# button_pad_6x10_v19.net
KiCad netlist of a schematic drawn in EAGLE
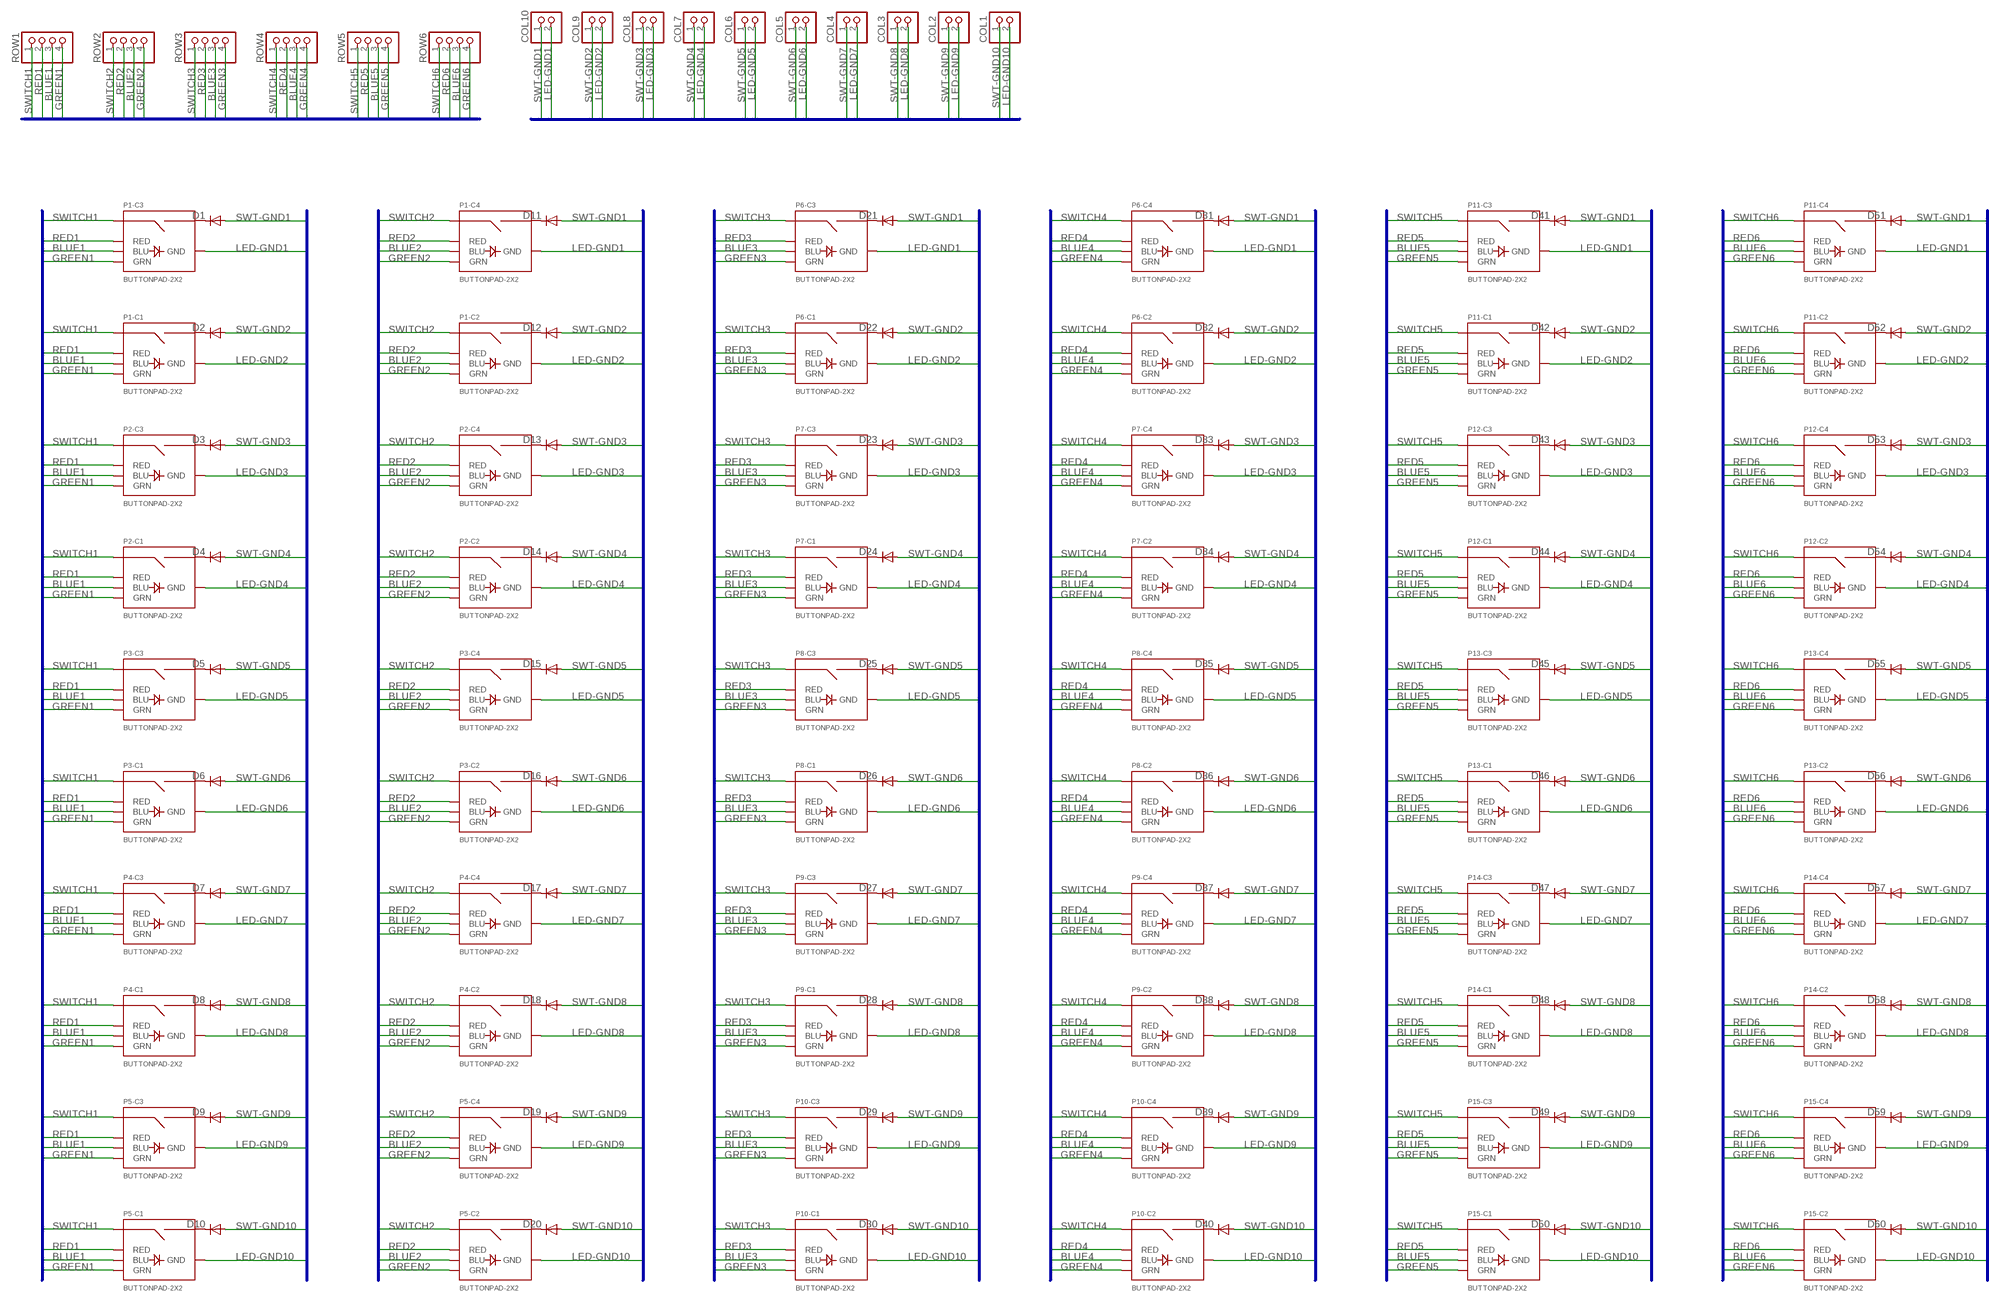
[diagram p0: schematic, sheet 1]

(export (version "E")
  (design (tool "Eeschema 10.0.6"))
  (components
    (comp (ref "COL1")
      (value "PINHD-1X2")
      (footprint "eagle-import:1X02")
      (libsource (lib "eagle-import") (part "PINHD-1X2"))
    )
    (comp (ref "COL2")
      (value "PINHD-1X2")
      (footprint "eagle-import:1X02")
      (libsource (lib "eagle-import") (part "PINHD-1X2"))
    )
    (comp (ref "COL3")
      (value "PINHD-1X2")
      (footprint "eagle-import:1X02")
      (libsource (lib "eagle-import") (part "PINHD-1X2"))
    )
    (comp (ref "COL4")
      (value "PINHD-1X2")
      (footprint "eagle-import:1X02")
      (libsource (lib "eagle-import") (part "PINHD-1X2"))
    )
    (comp (ref "COL5")
      (value "PINHD-1X2")
      (footprint "eagle-import:1X02")
      (libsource (lib "eagle-import") (part "PINHD-1X2"))
    )
    (comp (ref "COL6")
      (value "PINHD-1X2")
      (footprint "eagle-import:1X02")
      (libsource (lib "eagle-import") (part "PINHD-1X2"))
    )
    (comp (ref "COL7")
      (value "PINHD-1X2")
      (footprint "eagle-import:1X02")
      (libsource (lib "eagle-import") (part "PINHD-1X2"))
    )
    (comp (ref "COL8")
      (value "PINHD-1X2")
      (footprint "eagle-import:1X02")
      (libsource (lib "eagle-import") (part "PINHD-1X2"))
    )
    (comp (ref "COL9")
      (value "PINHD-1X2")
      (footprint "eagle-import:1X02")
      (libsource (lib "eagle-import") (part "PINHD-1X2"))
    )
    (comp (ref "COL10")
      (value "PINHD-1X2")
      (footprint "eagle-import:1X02")
      (libsource (lib "eagle-import") (part "PINHD-1X2"))
    )
    (comp (ref "D1")
      (value "DIODE-1N4148")
      (footprint "eagle-import:DOIDE-1N4148")
      (libsource (lib "eagle-import") (part "DIODE-1N4148"))
    )
    (comp (ref "D2")
      (value "DIODE-1N4148")
      (footprint "eagle-import:DOIDE-1N4148")
      (libsource (lib "eagle-import") (part "DIODE-1N4148"))
    )
    (comp (ref "D3")
      (value "DIODE-1N4148")
      (footprint "eagle-import:DOIDE-1N4148")
      (libsource (lib "eagle-import") (part "DIODE-1N4148"))
    )
    (comp (ref "D4")
      (value "DIODE-1N4148")
      (footprint "eagle-import:DOIDE-1N4148")
      (libsource (lib "eagle-import") (part "DIODE-1N4148"))
    )
    (comp (ref "D5")
      (value "DIODE-1N4148")
      (footprint "eagle-import:DOIDE-1N4148")
      (libsource (lib "eagle-import") (part "DIODE-1N4148"))
    )
    (comp (ref "D6")
      (value "DIODE-1N4148")
      (footprint "eagle-import:DOIDE-1N4148")
      (libsource (lib "eagle-import") (part "DIODE-1N4148"))
    )
    (comp (ref "D7")
      (value "DIODE-1N4148")
      (footprint "eagle-import:DOIDE-1N4148")
      (libsource (lib "eagle-import") (part "DIODE-1N4148"))
    )
    (comp (ref "D8")
      (value "DIODE-1N4148")
      (footprint "eagle-import:DOIDE-1N4148")
      (libsource (lib "eagle-import") (part "DIODE-1N4148"))
    )
    (comp (ref "D9")
      (value "DIODE-1N4148")
      (footprint "eagle-import:DOIDE-1N4148")
      (libsource (lib "eagle-import") (part "DIODE-1N4148"))
    )
    (comp (ref "D10")
      (value "DIODE-1N4148")
      (footprint "eagle-import:DOIDE-1N4148")
      (libsource (lib "eagle-import") (part "DIODE-1N4148"))
    )
    (comp (ref "D11")
      (value "DIODE-1N4148")
      (footprint "eagle-import:DOIDE-1N4148")
      (libsource (lib "eagle-import") (part "DIODE-1N4148"))
    )
    (comp (ref "D12")
      (value "DIODE-1N4148")
      (footprint "eagle-import:DOIDE-1N4148")
      (libsource (lib "eagle-import") (part "DIODE-1N4148"))
    )
    (comp (ref "D13")
      (value "DIODE-1N4148")
      (footprint "eagle-import:DOIDE-1N4148")
      (libsource (lib "eagle-import") (part "DIODE-1N4148"))
    )
    (comp (ref "D14")
      (value "DIODE-1N4148")
      (footprint "eagle-import:DOIDE-1N4148")
      (libsource (lib "eagle-import") (part "DIODE-1N4148"))
    )
    (comp (ref "D15")
      (value "DIODE-1N4148")
      (footprint "eagle-import:DOIDE-1N4148")
      (libsource (lib "eagle-import") (part "DIODE-1N4148"))
    )
    (comp (ref "D16")
      (value "DIODE-1N4148")
      (footprint "eagle-import:DOIDE-1N4148")
      (libsource (lib "eagle-import") (part "DIODE-1N4148"))
    )
    (comp (ref "D17")
      (value "DIODE-1N4148")
      (footprint "eagle-import:DOIDE-1N4148")
      (libsource (lib "eagle-import") (part "DIODE-1N4148"))
    )
    (comp (ref "D18")
      (value "DIODE-1N4148")
      (footprint "eagle-import:DOIDE-1N4148")
      (libsource (lib "eagle-import") (part "DIODE-1N4148"))
    )
    (comp (ref "D19")
      (value "DIODE-1N4148")
      (footprint "eagle-import:DOIDE-1N4148")
      (libsource (lib "eagle-import") (part "DIODE-1N4148"))
    )
    (comp (ref "D20")
      (value "DIODE-1N4148")
      (footprint "eagle-import:DOIDE-1N4148")
      (libsource (lib "eagle-import") (part "DIODE-1N4148"))
    )
    (comp (ref "D21")
      (value "DIODE-1N4148")
      (footprint "eagle-import:DOIDE-1N4148")
      (libsource (lib "eagle-import") (part "DIODE-1N4148"))
    )
    (comp (ref "D22")
      (value "DIODE-1N4148")
      (footprint "eagle-import:DOIDE-1N4148")
      (libsource (lib "eagle-import") (part "DIODE-1N4148"))
    )
    (comp (ref "D23")
      (value "DIODE-1N4148")
      (footprint "eagle-import:DOIDE-1N4148")
      (libsource (lib "eagle-import") (part "DIODE-1N4148"))
    )
    (comp (ref "D24")
      (value "DIODE-1N4148")
      (footprint "eagle-import:DOIDE-1N4148")
      (libsource (lib "eagle-import") (part "DIODE-1N4148"))
    )
    (comp (ref "D25")
      (value "DIODE-1N4148")
      (footprint "eagle-import:DOIDE-1N4148")
      (libsource (lib "eagle-import") (part "DIODE-1N4148"))
    )
    (comp (ref "D26")
      (value "DIODE-1N4148")
      (footprint "eagle-import:DOIDE-1N4148")
      (libsource (lib "eagle-import") (part "DIODE-1N4148"))
    )
    (comp (ref "D27")
      (value "DIODE-1N4148")
      (footprint "eagle-import:DOIDE-1N4148")
      (libsource (lib "eagle-import") (part "DIODE-1N4148"))
    )
    (comp (ref "D28")
      (value "DIODE-1N4148")
      (footprint "eagle-import:DOIDE-1N4148")
      (libsource (lib "eagle-import") (part "DIODE-1N4148"))
    )
    (comp (ref "D29")
      (value "DIODE-1N4148")
      (footprint "eagle-import:DOIDE-1N4148")
      (libsource (lib "eagle-import") (part "DIODE-1N4148"))
    )
    (comp (ref "D30")
      (value "DIODE-1N4148")
      (footprint "eagle-import:DOIDE-1N4148")
      (libsource (lib "eagle-import") (part "DIODE-1N4148"))
    )
    (comp (ref "D31")
      (value "DIODE-1N4148")
      (footprint "eagle-import:DOIDE-1N4148")
      (libsource (lib "eagle-import") (part "DIODE-1N4148"))
    )
    (comp (ref "D32")
      (value "DIODE-1N4148")
      (footprint "eagle-import:DOIDE-1N4148")
      (libsource (lib "eagle-import") (part "DIODE-1N4148"))
    )
    (comp (ref "D33")
      (value "DIODE-1N4148")
      (footprint "eagle-import:DOIDE-1N4148")
      (libsource (lib "eagle-import") (part "DIODE-1N4148"))
    )
    (comp (ref "D34")
      (value "DIODE-1N4148")
      (footprint "eagle-import:DOIDE-1N4148")
      (libsource (lib "eagle-import") (part "DIODE-1N4148"))
    )
    (comp (ref "D35")
      (value "DIODE-1N4148")
      (footprint "eagle-import:DOIDE-1N4148")
      (libsource (lib "eagle-import") (part "DIODE-1N4148"))
    )
    (comp (ref "D36")
      (value "DIODE-1N4148")
      (footprint "eagle-import:DOIDE-1N4148")
      (libsource (lib "eagle-import") (part "DIODE-1N4148"))
    )
    (comp (ref "D37")
      (value "DIODE-1N4148")
      (footprint "eagle-import:DOIDE-1N4148")
      (libsource (lib "eagle-import") (part "DIODE-1N4148"))
    )
    (comp (ref "D38")
      (value "DIODE-1N4148")
      (footprint "eagle-import:DOIDE-1N4148")
      (libsource (lib "eagle-import") (part "DIODE-1N4148"))
    )
    (comp (ref "D39")
      (value "DIODE-1N4148")
      (footprint "eagle-import:DOIDE-1N4148")
      (libsource (lib "eagle-import") (part "DIODE-1N4148"))
    )
    (comp (ref "D40")
      (value "DIODE-1N4148")
      (footprint "eagle-import:DOIDE-1N4148")
      (libsource (lib "eagle-import") (part "DIODE-1N4148"))
    )
    (comp (ref "D41")
      (value "DIODE-1N4148")
      (footprint "eagle-import:DOIDE-1N4148")
      (libsource (lib "eagle-import") (part "DIODE-1N4148"))
    )
    (comp (ref "D42")
      (value "DIODE-1N4148")
      (footprint "eagle-import:DOIDE-1N4148")
      (libsource (lib "eagle-import") (part "DIODE-1N4148"))
    )
    (comp (ref "D43")
      (value "DIODE-1N4148")
      (footprint "eagle-import:DOIDE-1N4148")
      (libsource (lib "eagle-import") (part "DIODE-1N4148"))
    )
    (comp (ref "D44")
      (value "DIODE-1N4148")
      (footprint "eagle-import:DOIDE-1N4148")
      (libsource (lib "eagle-import") (part "DIODE-1N4148"))
    )
    (comp (ref "D45")
      (value "DIODE-1N4148")
      (footprint "eagle-import:DOIDE-1N4148")
      (libsource (lib "eagle-import") (part "DIODE-1N4148"))
    )
    (comp (ref "D46")
      (value "DIODE-1N4148")
      (footprint "eagle-import:DOIDE-1N4148")
      (libsource (lib "eagle-import") (part "DIODE-1N4148"))
    )
    (comp (ref "D47")
      (value "DIODE-1N4148")
      (footprint "eagle-import:DOIDE-1N4148")
      (libsource (lib "eagle-import") (part "DIODE-1N4148"))
    )
    (comp (ref "D48")
      (value "DIODE-1N4148")
      (footprint "eagle-import:DOIDE-1N4148")
      (libsource (lib "eagle-import") (part "DIODE-1N4148"))
    )
    (comp (ref "D49")
      (value "DIODE-1N4148")
      (footprint "eagle-import:DOIDE-1N4148")
      (libsource (lib "eagle-import") (part "DIODE-1N4148"))
    )
    (comp (ref "D50")
      (value "DIODE-1N4148")
      (footprint "eagle-import:DOIDE-1N4148")
      (libsource (lib "eagle-import") (part "DIODE-1N4148"))
    )
    (comp (ref "D51")
      (value "DIODE-1N4148")
      (footprint "eagle-import:DOIDE-1N4148")
      (libsource (lib "eagle-import") (part "DIODE-1N4148"))
    )
    (comp (ref "D52")
      (value "DIODE-1N4148")
      (footprint "eagle-import:DOIDE-1N4148")
      (libsource (lib "eagle-import") (part "DIODE-1N4148"))
    )
    (comp (ref "D53")
      (value "DIODE-1N4148")
      (footprint "eagle-import:DOIDE-1N4148")
      (libsource (lib "eagle-import") (part "DIODE-1N4148"))
    )
    (comp (ref "D54")
      (value "DIODE-1N4148")
      (footprint "eagle-import:DOIDE-1N4148")
      (libsource (lib "eagle-import") (part "DIODE-1N4148"))
    )
    (comp (ref "D55")
      (value "DIODE-1N4148")
      (footprint "eagle-import:DOIDE-1N4148")
      (libsource (lib "eagle-import") (part "DIODE-1N4148"))
    )
    (comp (ref "D56")
      (value "DIODE-1N4148")
      (footprint "eagle-import:DOIDE-1N4148")
      (libsource (lib "eagle-import") (part "DIODE-1N4148"))
    )
    (comp (ref "D57")
      (value "DIODE-1N4148")
      (footprint "eagle-import:DOIDE-1N4148")
      (libsource (lib "eagle-import") (part "DIODE-1N4148"))
    )
    (comp (ref "D58")
      (value "DIODE-1N4148")
      (footprint "eagle-import:DOIDE-1N4148")
      (libsource (lib "eagle-import") (part "DIODE-1N4148"))
    )
    (comp (ref "D59")
      (value "DIODE-1N4148")
      (footprint "eagle-import:DOIDE-1N4148")
      (libsource (lib "eagle-import") (part "DIODE-1N4148"))
    )
    (comp (ref "D60")
      (value "DIODE-1N4148")
      (footprint "eagle-import:DOIDE-1N4148")
      (libsource (lib "eagle-import") (part "DIODE-1N4148"))
    )
    (comp (ref "P1")
      (value "BUTTONPAD-2X2")
      (footprint "eagle-import:BUTTONPAD-2X2")
      (libsource (lib "eagle-import") (part "BUTTONPAD-2X2"))
    )
    (comp (ref "P2")
      (value "BUTTONPAD-2X2")
      (footprint "eagle-import:BUTTONPAD-2X2")
      (libsource (lib "eagle-import") (part "BUTTONPAD-2X2"))
    )
    (comp (ref "P3")
      (value "BUTTONPAD-2X2")
      (footprint "eagle-import:BUTTONPAD-2X2")
      (libsource (lib "eagle-import") (part "BUTTONPAD-2X2"))
    )
    (comp (ref "P4")
      (value "BUTTONPAD-2X2")
      (footprint "eagle-import:BUTTONPAD-2X2")
      (libsource (lib "eagle-import") (part "BUTTONPAD-2X2"))
    )
    (comp (ref "P5")
      (value "BUTTONPAD-2X2")
      (footprint "eagle-import:BUTTONPAD-2X2")
      (libsource (lib "eagle-import") (part "BUTTONPAD-2X2"))
    )
    (comp (ref "P6")
      (value "BUTTONPAD-2X2")
      (footprint "eagle-import:BUTTONPAD-2X2")
      (libsource (lib "eagle-import") (part "BUTTONPAD-2X2"))
    )
    (comp (ref "P7")
      (value "BUTTONPAD-2X2")
      (footprint "eagle-import:BUTTONPAD-2X2")
      (libsource (lib "eagle-import") (part "BUTTONPAD-2X2"))
    )
    (comp (ref "P8")
      (value "BUTTONPAD-2X2")
      (footprint "eagle-import:BUTTONPAD-2X2")
      (libsource (lib "eagle-import") (part "BUTTONPAD-2X2"))
    )
    (comp (ref "P9")
      (value "BUTTONPAD-2X2")
      (footprint "eagle-import:BUTTONPAD-2X2")
      (libsource (lib "eagle-import") (part "BUTTONPAD-2X2"))
    )
    (comp (ref "P10")
      (value "BUTTONPAD-2X2")
      (footprint "eagle-import:BUTTONPAD-2X2")
      (libsource (lib "eagle-import") (part "BUTTONPAD-2X2"))
    )
    (comp (ref "P11")
      (value "BUTTONPAD-2X2")
      (footprint "eagle-import:BUTTONPAD-2X2")
      (libsource (lib "eagle-import") (part "BUTTONPAD-2X2"))
    )
    (comp (ref "P12")
      (value "BUTTONPAD-2X2")
      (footprint "eagle-import:BUTTONPAD-2X2")
      (libsource (lib "eagle-import") (part "BUTTONPAD-2X2"))
    )
    (comp (ref "P13")
      (value "BUTTONPAD-2X2")
      (footprint "eagle-import:BUTTONPAD-2X2")
      (libsource (lib "eagle-import") (part "BUTTONPAD-2X2"))
    )
    (comp (ref "P14")
      (value "BUTTONPAD-2X2")
      (footprint "eagle-import:BUTTONPAD-2X2")
      (libsource (lib "eagle-import") (part "BUTTONPAD-2X2"))
    )
    (comp (ref "P15")
      (value "BUTTONPAD-2X2")
      (footprint "eagle-import:BUTTONPAD-2X2")
      (libsource (lib "eagle-import") (part "BUTTONPAD-2X2"))
    )
    (comp (ref "ROW1")
      (value "PINHD-1X4")
      (footprint "eagle-import:1X04")
      (libsource (lib "eagle-import") (part "PINHD-1X4"))
    )
    (comp (ref "ROW2")
      (value "PINHD-1X4")
      (footprint "eagle-import:1X04")
      (libsource (lib "eagle-import") (part "PINHD-1X4"))
    )
    (comp (ref "ROW3")
      (value "PINHD-1X4")
      (footprint "eagle-import:1X04")
      (libsource (lib "eagle-import") (part "PINHD-1X4"))
    )
    (comp (ref "ROW4")
      (value "PINHD-1X4")
      (footprint "eagle-import:1X04")
      (libsource (lib "eagle-import") (part "PINHD-1X4"))
    )
    (comp (ref "ROW5")
      (value "PINHD-1X4")
      (footprint "eagle-import:1X04")
      (libsource (lib "eagle-import") (part "PINHD-1X4"))
    )
    (comp (ref "ROW6")
      (value "PINHD-1X4")
      (footprint "eagle-import:1X04")
      (libsource (lib "eagle-import") (part "PINHD-1X4"))
    )
  )
  (nets
    (net (code "1") (name "/BLUE1") (class "Default")
      (node (ref "P1") (pin "BLU1") (pinfunction "BLU_BLU1") (pintype "bidirectional"))
      (node (ref "P1") (pin "BLU3") (pinfunction "BLU_BLU3") (pintype "bidirectional"))
      (node (ref "P2") (pin "BLU1") (pinfunction "BLU_BLU1") (pintype "bidirectional"))
      (node (ref "P2") (pin "BLU3") (pinfunction "BLU_BLU3") (pintype "bidirectional"))
      (node (ref "P3") (pin "BLU1") (pinfunction "BLU_BLU1") (pintype "bidirectional"))
      (node (ref "P3") (pin "BLU3") (pinfunction "BLU_BLU3") (pintype "bidirectional"))
      (node (ref "P4") (pin "BLU1") (pinfunction "BLU_BLU1") (pintype "bidirectional"))
      (node (ref "P4") (pin "BLU3") (pinfunction "BLU_BLU3") (pintype "bidirectional"))
      (node (ref "P5") (pin "BLU1") (pinfunction "BLU_BLU1") (pintype "bidirectional"))
      (node (ref "P5") (pin "BLU3") (pinfunction "BLU_BLU3") (pintype "bidirectional"))
      (node (ref "ROW1") (pin "3") (pinfunction "3_3") (pintype "passive"))
    )
    (net (code "2") (name "/BLUE2") (class "Default")
      (node (ref "P1") (pin "BLU2") (pinfunction "BLU_BLU2") (pintype "bidirectional"))
      (node (ref "P1") (pin "BLU4") (pinfunction "BLU_BLU4") (pintype "bidirectional"))
      (node (ref "P2") (pin "BLU2") (pinfunction "BLU_BLU2") (pintype "bidirectional"))
      (node (ref "P2") (pin "BLU4") (pinfunction "BLU_BLU4") (pintype "bidirectional"))
      (node (ref "P3") (pin "BLU2") (pinfunction "BLU_BLU2") (pintype "bidirectional"))
      (node (ref "P3") (pin "BLU4") (pinfunction "BLU_BLU4") (pintype "bidirectional"))
      (node (ref "P4") (pin "BLU2") (pinfunction "BLU_BLU2") (pintype "bidirectional"))
      (node (ref "P4") (pin "BLU4") (pinfunction "BLU_BLU4") (pintype "bidirectional"))
      (node (ref "P5") (pin "BLU2") (pinfunction "BLU_BLU2") (pintype "bidirectional"))
      (node (ref "P5") (pin "BLU4") (pinfunction "BLU_BLU4") (pintype "bidirectional"))
      (node (ref "ROW2") (pin "3") (pinfunction "3_3") (pintype "passive"))
    )
    (net (code "3") (name "/BLUE3") (class "Default")
      (node (ref "P10") (pin "BLU1") (pinfunction "BLU_BLU1") (pintype "bidirectional"))
      (node (ref "P10") (pin "BLU3") (pinfunction "BLU_BLU3") (pintype "bidirectional"))
      (node (ref "P6") (pin "BLU1") (pinfunction "BLU_BLU1") (pintype "bidirectional"))
      (node (ref "P6") (pin "BLU3") (pinfunction "BLU_BLU3") (pintype "bidirectional"))
      (node (ref "P7") (pin "BLU1") (pinfunction "BLU_BLU1") (pintype "bidirectional"))
      (node (ref "P7") (pin "BLU3") (pinfunction "BLU_BLU3") (pintype "bidirectional"))
      (node (ref "P8") (pin "BLU1") (pinfunction "BLU_BLU1") (pintype "bidirectional"))
      (node (ref "P8") (pin "BLU3") (pinfunction "BLU_BLU3") (pintype "bidirectional"))
      (node (ref "P9") (pin "BLU1") (pinfunction "BLU_BLU1") (pintype "bidirectional"))
      (node (ref "P9") (pin "BLU3") (pinfunction "BLU_BLU3") (pintype "bidirectional"))
      (node (ref "ROW3") (pin "3") (pinfunction "3_3") (pintype "passive"))
    )
    (net (code "4") (name "/BLUE4") (class "Default")
      (node (ref "P10") (pin "BLU2") (pinfunction "BLU_BLU2") (pintype "bidirectional"))
      (node (ref "P10") (pin "BLU4") (pinfunction "BLU_BLU4") (pintype "bidirectional"))
      (node (ref "P6") (pin "BLU2") (pinfunction "BLU_BLU2") (pintype "bidirectional"))
      (node (ref "P6") (pin "BLU4") (pinfunction "BLU_BLU4") (pintype "bidirectional"))
      (node (ref "P7") (pin "BLU2") (pinfunction "BLU_BLU2") (pintype "bidirectional"))
      (node (ref "P7") (pin "BLU4") (pinfunction "BLU_BLU4") (pintype "bidirectional"))
      (node (ref "P8") (pin "BLU2") (pinfunction "BLU_BLU2") (pintype "bidirectional"))
      (node (ref "P8") (pin "BLU4") (pinfunction "BLU_BLU4") (pintype "bidirectional"))
      (node (ref "P9") (pin "BLU2") (pinfunction "BLU_BLU2") (pintype "bidirectional"))
      (node (ref "P9") (pin "BLU4") (pinfunction "BLU_BLU4") (pintype "bidirectional"))
      (node (ref "ROW4") (pin "3") (pinfunction "3_3") (pintype "passive"))
    )
    (net (code "5") (name "/BLUE5") (class "Default")
      (node (ref "P11") (pin "BLU1") (pinfunction "BLU_BLU1") (pintype "bidirectional"))
      (node (ref "P11") (pin "BLU3") (pinfunction "BLU_BLU3") (pintype "bidirectional"))
      (node (ref "P12") (pin "BLU1") (pinfunction "BLU_BLU1") (pintype "bidirectional"))
      (node (ref "P12") (pin "BLU3") (pinfunction "BLU_BLU3") (pintype "bidirectional"))
      (node (ref "P13") (pin "BLU1") (pinfunction "BLU_BLU1") (pintype "bidirectional"))
      (node (ref "P13") (pin "BLU3") (pinfunction "BLU_BLU3") (pintype "bidirectional"))
      (node (ref "P14") (pin "BLU1") (pinfunction "BLU_BLU1") (pintype "bidirectional"))
      (node (ref "P14") (pin "BLU3") (pinfunction "BLU_BLU3") (pintype "bidirectional"))
      (node (ref "P15") (pin "BLU1") (pinfunction "BLU_BLU1") (pintype "bidirectional"))
      (node (ref "P15") (pin "BLU3") (pinfunction "BLU_BLU3") (pintype "bidirectional"))
      (node (ref "ROW5") (pin "3") (pinfunction "3_3") (pintype "passive"))
    )
    (net (code "6") (name "/BLUE6") (class "Default")
      (node (ref "P11") (pin "BLU2") (pinfunction "BLU_BLU2") (pintype "bidirectional"))
      (node (ref "P11") (pin "BLU4") (pinfunction "BLU_BLU4") (pintype "bidirectional"))
      (node (ref "P12") (pin "BLU2") (pinfunction "BLU_BLU2") (pintype "bidirectional"))
      (node (ref "P12") (pin "BLU4") (pinfunction "BLU_BLU4") (pintype "bidirectional"))
      (node (ref "P13") (pin "BLU2") (pinfunction "BLU_BLU2") (pintype "bidirectional"))
      (node (ref "P13") (pin "BLU4") (pinfunction "BLU_BLU4") (pintype "bidirectional"))
      (node (ref "P14") (pin "BLU2") (pinfunction "BLU_BLU2") (pintype "bidirectional"))
      (node (ref "P14") (pin "BLU4") (pinfunction "BLU_BLU4") (pintype "bidirectional"))
      (node (ref "P15") (pin "BLU2") (pinfunction "BLU_BLU2") (pintype "bidirectional"))
      (node (ref "P15") (pin "BLU4") (pinfunction "BLU_BLU4") (pintype "bidirectional"))
      (node (ref "ROW6") (pin "3") (pinfunction "3_3") (pintype "passive"))
    )
    (net (code "7") (name "/GREEN1") (class "Default")
      (node (ref "P1") (pin "GRN1") (pinfunction "GRN_GRN1") (pintype "bidirectional"))
      (node (ref "P1") (pin "GRN3") (pinfunction "GRN_GRN3") (pintype "bidirectional"))
      (node (ref "P2") (pin "GRN1") (pinfunction "GRN_GRN1") (pintype "bidirectional"))
      (node (ref "P2") (pin "GRN3") (pinfunction "GRN_GRN3") (pintype "bidirectional"))
      (node (ref "P3") (pin "GRN1") (pinfunction "GRN_GRN1") (pintype "bidirectional"))
      (node (ref "P3") (pin "GRN3") (pinfunction "GRN_GRN3") (pintype "bidirectional"))
      (node (ref "P4") (pin "GRN1") (pinfunction "GRN_GRN1") (pintype "bidirectional"))
      (node (ref "P4") (pin "GRN3") (pinfunction "GRN_GRN3") (pintype "bidirectional"))
      (node (ref "P5") (pin "GRN1") (pinfunction "GRN_GRN1") (pintype "bidirectional"))
      (node (ref "P5") (pin "GRN3") (pinfunction "GRN_GRN3") (pintype "bidirectional"))
      (node (ref "ROW1") (pin "4") (pinfunction "4_4") (pintype "passive"))
    )
    (net (code "8") (name "/GREEN2") (class "Default")
      (node (ref "P1") (pin "GRN2") (pinfunction "GRN_GRN2") (pintype "bidirectional"))
      (node (ref "P1") (pin "GRN4") (pinfunction "GRN_GRN4") (pintype "bidirectional"))
      (node (ref "P2") (pin "GRN2") (pinfunction "GRN_GRN2") (pintype "bidirectional"))
      (node (ref "P2") (pin "GRN4") (pinfunction "GRN_GRN4") (pintype "bidirectional"))
      (node (ref "P3") (pin "GRN2") (pinfunction "GRN_GRN2") (pintype "bidirectional"))
      (node (ref "P3") (pin "GRN4") (pinfunction "GRN_GRN4") (pintype "bidirectional"))
      (node (ref "P4") (pin "GRN2") (pinfunction "GRN_GRN2") (pintype "bidirectional"))
      (node (ref "P4") (pin "GRN4") (pinfunction "GRN_GRN4") (pintype "bidirectional"))
      (node (ref "P5") (pin "GRN2") (pinfunction "GRN_GRN2") (pintype "bidirectional"))
      (node (ref "P5") (pin "GRN4") (pinfunction "GRN_GRN4") (pintype "bidirectional"))
      (node (ref "ROW2") (pin "4") (pinfunction "4_4") (pintype "passive"))
    )
    (net (code "9") (name "/GREEN3") (class "Default")
      (node (ref "P10") (pin "GRN1") (pinfunction "GRN_GRN1") (pintype "bidirectional"))
      (node (ref "P10") (pin "GRN3") (pinfunction "GRN_GRN3") (pintype "bidirectional"))
      (node (ref "P6") (pin "GRN1") (pinfunction "GRN_GRN1") (pintype "bidirectional"))
      (node (ref "P6") (pin "GRN3") (pinfunction "GRN_GRN3") (pintype "bidirectional"))
      (node (ref "P7") (pin "GRN1") (pinfunction "GRN_GRN1") (pintype "bidirectional"))
      (node (ref "P7") (pin "GRN3") (pinfunction "GRN_GRN3") (pintype "bidirectional"))
      (node (ref "P8") (pin "GRN1") (pinfunction "GRN_GRN1") (pintype "bidirectional"))
      (node (ref "P8") (pin "GRN3") (pinfunction "GRN_GRN3") (pintype "bidirectional"))
      (node (ref "P9") (pin "GRN1") (pinfunction "GRN_GRN1") (pintype "bidirectional"))
      (node (ref "P9") (pin "GRN3") (pinfunction "GRN_GRN3") (pintype "bidirectional"))
      (node (ref "ROW3") (pin "4") (pinfunction "4_4") (pintype "passive"))
    )
    (net (code "10") (name "/GREEN4") (class "Default")
      (node (ref "P10") (pin "GRN2") (pinfunction "GRN_GRN2") (pintype "bidirectional"))
      (node (ref "P10") (pin "GRN4") (pinfunction "GRN_GRN4") (pintype "bidirectional"))
      (node (ref "P6") (pin "GRN2") (pinfunction "GRN_GRN2") (pintype "bidirectional"))
      (node (ref "P6") (pin "GRN4") (pinfunction "GRN_GRN4") (pintype "bidirectional"))
      (node (ref "P7") (pin "GRN2") (pinfunction "GRN_GRN2") (pintype "bidirectional"))
      (node (ref "P7") (pin "GRN4") (pinfunction "GRN_GRN4") (pintype "bidirectional"))
      (node (ref "P8") (pin "GRN2") (pinfunction "GRN_GRN2") (pintype "bidirectional"))
      (node (ref "P8") (pin "GRN4") (pinfunction "GRN_GRN4") (pintype "bidirectional"))
      (node (ref "P9") (pin "GRN2") (pinfunction "GRN_GRN2") (pintype "bidirectional"))
      (node (ref "P9") (pin "GRN4") (pinfunction "GRN_GRN4") (pintype "bidirectional"))
      (node (ref "ROW4") (pin "4") (pinfunction "4_4") (pintype "passive"))
    )
    (net (code "11") (name "/GREEN5") (class "Default")
      (node (ref "P11") (pin "GRN1") (pinfunction "GRN_GRN1") (pintype "bidirectional"))
      (node (ref "P11") (pin "GRN3") (pinfunction "GRN_GRN3") (pintype "bidirectional"))
      (node (ref "P12") (pin "GRN1") (pinfunction "GRN_GRN1") (pintype "bidirectional"))
      (node (ref "P12") (pin "GRN3") (pinfunction "GRN_GRN3") (pintype "bidirectional"))
      (node (ref "P13") (pin "GRN1") (pinfunction "GRN_GRN1") (pintype "bidirectional"))
      (node (ref "P13") (pin "GRN3") (pinfunction "GRN_GRN3") (pintype "bidirectional"))
      (node (ref "P14") (pin "GRN1") (pinfunction "GRN_GRN1") (pintype "bidirectional"))
      (node (ref "P14") (pin "GRN3") (pinfunction "GRN_GRN3") (pintype "bidirectional"))
      (node (ref "P15") (pin "GRN1") (pinfunction "GRN_GRN1") (pintype "bidirectional"))
      (node (ref "P15") (pin "GRN3") (pinfunction "GRN_GRN3") (pintype "bidirectional"))
      (node (ref "ROW5") (pin "4") (pinfunction "4_4") (pintype "passive"))
    )
    (net (code "12") (name "/GREEN6") (class "Default")
      (node (ref "P11") (pin "GRN2") (pinfunction "GRN_GRN2") (pintype "bidirectional"))
      (node (ref "P11") (pin "GRN4") (pinfunction "GRN_GRN4") (pintype "bidirectional"))
      (node (ref "P12") (pin "GRN2") (pinfunction "GRN_GRN2") (pintype "bidirectional"))
      (node (ref "P12") (pin "GRN4") (pinfunction "GRN_GRN4") (pintype "bidirectional"))
      (node (ref "P13") (pin "GRN2") (pinfunction "GRN_GRN2") (pintype "bidirectional"))
      (node (ref "P13") (pin "GRN4") (pinfunction "GRN_GRN4") (pintype "bidirectional"))
      (node (ref "P14") (pin "GRN2") (pinfunction "GRN_GRN2") (pintype "bidirectional"))
      (node (ref "P14") (pin "GRN4") (pinfunction "GRN_GRN4") (pintype "bidirectional"))
      (node (ref "P15") (pin "GRN2") (pinfunction "GRN_GRN2") (pintype "bidirectional"))
      (node (ref "P15") (pin "GRN4") (pinfunction "GRN_GRN4") (pintype "bidirectional"))
      (node (ref "ROW6") (pin "4") (pinfunction "4_4") (pintype "passive"))
    )
    (net (code "13") (name "/LED-GND1") (class "Default")
      (node (ref "COL10") (pin "2") (pinfunction "2_2") (pintype "passive"))
      (node (ref "P1") (pin "GND3") (pinfunction "GND_GND3") (pintype "bidirectional"))
      (node (ref "P1") (pin "GND4") (pinfunction "GND_GND4") (pintype "bidirectional"))
      (node (ref "P11") (pin "GND3") (pinfunction "GND_GND3") (pintype "bidirectional"))
      (node (ref "P11") (pin "GND4") (pinfunction "GND_GND4") (pintype "bidirectional"))
      (node (ref "P6") (pin "GND3") (pinfunction "GND_GND3") (pintype "bidirectional"))
      (node (ref "P6") (pin "GND4") (pinfunction "GND_GND4") (pintype "bidirectional"))
    )
    (net (code "14") (name "/LED-GND2") (class "Default")
      (node (ref "COL9") (pin "2") (pinfunction "2_2") (pintype "passive"))
      (node (ref "P1") (pin "GND1") (pinfunction "GND_GND1") (pintype "bidirectional"))
      (node (ref "P1") (pin "GND2") (pinfunction "GND_GND2") (pintype "bidirectional"))
      (node (ref "P11") (pin "GND1") (pinfunction "GND_GND1") (pintype "bidirectional"))
      (node (ref "P11") (pin "GND2") (pinfunction "GND_GND2") (pintype "bidirectional"))
      (node (ref "P6") (pin "GND1") (pinfunction "GND_GND1") (pintype "bidirectional"))
      (node (ref "P6") (pin "GND2") (pinfunction "GND_GND2") (pintype "bidirectional"))
    )
    (net (code "15") (name "/LED-GND3") (class "Default")
      (node (ref "COL8") (pin "2") (pinfunction "2_2") (pintype "passive"))
      (node (ref "P12") (pin "GND3") (pinfunction "GND_GND3") (pintype "bidirectional"))
      (node (ref "P12") (pin "GND4") (pinfunction "GND_GND4") (pintype "bidirectional"))
      (node (ref "P2") (pin "GND3") (pinfunction "GND_GND3") (pintype "bidirectional"))
      (node (ref "P2") (pin "GND4") (pinfunction "GND_GND4") (pintype "bidirectional"))
      (node (ref "P7") (pin "GND3") (pinfunction "GND_GND3") (pintype "bidirectional"))
      (node (ref "P7") (pin "GND4") (pinfunction "GND_GND4") (pintype "bidirectional"))
    )
    (net (code "16") (name "/LED-GND4") (class "Default")
      (node (ref "COL7") (pin "2") (pinfunction "2_2") (pintype "passive"))
      (node (ref "P12") (pin "GND1") (pinfunction "GND_GND1") (pintype "bidirectional"))
      (node (ref "P12") (pin "GND2") (pinfunction "GND_GND2") (pintype "bidirectional"))
      (node (ref "P2") (pin "GND1") (pinfunction "GND_GND1") (pintype "bidirectional"))
      (node (ref "P2") (pin "GND2") (pinfunction "GND_GND2") (pintype "bidirectional"))
      (node (ref "P7") (pin "GND1") (pinfunction "GND_GND1") (pintype "bidirectional"))
      (node (ref "P7") (pin "GND2") (pinfunction "GND_GND2") (pintype "bidirectional"))
    )
    (net (code "17") (name "/LED-GND5") (class "Default")
      (node (ref "COL6") (pin "2") (pinfunction "2_2") (pintype "passive"))
      (node (ref "P13") (pin "GND3") (pinfunction "GND_GND3") (pintype "bidirectional"))
      (node (ref "P13") (pin "GND4") (pinfunction "GND_GND4") (pintype "bidirectional"))
      (node (ref "P3") (pin "GND3") (pinfunction "GND_GND3") (pintype "bidirectional"))
      (node (ref "P3") (pin "GND4") (pinfunction "GND_GND4") (pintype "bidirectional"))
      (node (ref "P8") (pin "GND3") (pinfunction "GND_GND3") (pintype "bidirectional"))
      (node (ref "P8") (pin "GND4") (pinfunction "GND_GND4") (pintype "bidirectional"))
    )
    (net (code "18") (name "/LED-GND6") (class "Default")
      (node (ref "COL5") (pin "2") (pinfunction "2_2") (pintype "passive"))
      (node (ref "P13") (pin "GND1") (pinfunction "GND_GND1") (pintype "bidirectional"))
      (node (ref "P13") (pin "GND2") (pinfunction "GND_GND2") (pintype "bidirectional"))
      (node (ref "P3") (pin "GND1") (pinfunction "GND_GND1") (pintype "bidirectional"))
      (node (ref "P3") (pin "GND2") (pinfunction "GND_GND2") (pintype "bidirectional"))
      (node (ref "P8") (pin "GND1") (pinfunction "GND_GND1") (pintype "bidirectional"))
      (node (ref "P8") (pin "GND2") (pinfunction "GND_GND2") (pintype "bidirectional"))
    )
    (net (code "19") (name "/LED-GND7") (class "Default")
      (node (ref "COL4") (pin "2") (pinfunction "2_2") (pintype "passive"))
      (node (ref "P14") (pin "GND3") (pinfunction "GND_GND3") (pintype "bidirectional"))
      (node (ref "P14") (pin "GND4") (pinfunction "GND_GND4") (pintype "bidirectional"))
      (node (ref "P4") (pin "GND3") (pinfunction "GND_GND3") (pintype "bidirectional"))
      (node (ref "P4") (pin "GND4") (pinfunction "GND_GND4") (pintype "bidirectional"))
      (node (ref "P9") (pin "GND3") (pinfunction "GND_GND3") (pintype "bidirectional"))
      (node (ref "P9") (pin "GND4") (pinfunction "GND_GND4") (pintype "bidirectional"))
    )
    (net (code "20") (name "/LED-GND8") (class "Default")
      (node (ref "COL3") (pin "2") (pinfunction "2_2") (pintype "passive"))
      (node (ref "P14") (pin "GND1") (pinfunction "GND_GND1") (pintype "bidirectional"))
      (node (ref "P14") (pin "GND2") (pinfunction "GND_GND2") (pintype "bidirectional"))
      (node (ref "P4") (pin "GND1") (pinfunction "GND_GND1") (pintype "bidirectional"))
      (node (ref "P4") (pin "GND2") (pinfunction "GND_GND2") (pintype "bidirectional"))
      (node (ref "P9") (pin "GND1") (pinfunction "GND_GND1") (pintype "bidirectional"))
      (node (ref "P9") (pin "GND2") (pinfunction "GND_GND2") (pintype "bidirectional"))
    )
    (net (code "21") (name "/LED-GND9") (class "Default")
      (node (ref "COL2") (pin "2") (pinfunction "2_2") (pintype "passive"))
      (node (ref "P10") (pin "GND3") (pinfunction "GND_GND3") (pintype "bidirectional"))
      (node (ref "P10") (pin "GND4") (pinfunction "GND_GND4") (pintype "bidirectional"))
      (node (ref "P15") (pin "GND3") (pinfunction "GND_GND3") (pintype "bidirectional"))
      (node (ref "P15") (pin "GND4") (pinfunction "GND_GND4") (pintype "bidirectional"))
      (node (ref "P5") (pin "GND3") (pinfunction "GND_GND3") (pintype "bidirectional"))
      (node (ref "P5") (pin "GND4") (pinfunction "GND_GND4") (pintype "bidirectional"))
    )
    (net (code "22") (name "/LED-GND10") (class "Default")
      (node (ref "COL1") (pin "2") (pinfunction "2_2") (pintype "passive"))
      (node (ref "P10") (pin "GND1") (pinfunction "GND_GND1") (pintype "bidirectional"))
      (node (ref "P10") (pin "GND2") (pinfunction "GND_GND2") (pintype "bidirectional"))
      (node (ref "P15") (pin "GND1") (pinfunction "GND_GND1") (pintype "bidirectional"))
      (node (ref "P15") (pin "GND2") (pinfunction "GND_GND2") (pintype "bidirectional"))
      (node (ref "P5") (pin "GND1") (pinfunction "GND_GND1") (pintype "bidirectional"))
      (node (ref "P5") (pin "GND2") (pinfunction "GND_GND2") (pintype "bidirectional"))
    )
    (net (code "23") (name "/RED1") (class "Default")
      (node (ref "P1") (pin "RED1") (pinfunction "RED_RED1") (pintype "bidirectional"))
      (node (ref "P1") (pin "RED3") (pinfunction "RED_RED3") (pintype "bidirectional"))
      (node (ref "P2") (pin "RED1") (pinfunction "RED_RED1") (pintype "bidirectional"))
      (node (ref "P2") (pin "RED3") (pinfunction "RED_RED3") (pintype "bidirectional"))
      (node (ref "P3") (pin "RED1") (pinfunction "RED_RED1") (pintype "bidirectional"))
      (node (ref "P3") (pin "RED3") (pinfunction "RED_RED3") (pintype "bidirectional"))
      (node (ref "P4") (pin "RED1") (pinfunction "RED_RED1") (pintype "bidirectional"))
      (node (ref "P4") (pin "RED3") (pinfunction "RED_RED3") (pintype "bidirectional"))
      (node (ref "P5") (pin "RED1") (pinfunction "RED_RED1") (pintype "bidirectional"))
      (node (ref "P5") (pin "RED3") (pinfunction "RED_RED3") (pintype "bidirectional"))
      (node (ref "ROW1") (pin "2") (pinfunction "2_2") (pintype "passive"))
    )
    (net (code "24") (name "/RED2") (class "Default")
      (node (ref "P1") (pin "RED2") (pinfunction "RED_RED2") (pintype "bidirectional"))
      (node (ref "P1") (pin "RED4") (pinfunction "RED_RED4") (pintype "bidirectional"))
      (node (ref "P2") (pin "RED2") (pinfunction "RED_RED2") (pintype "bidirectional"))
      (node (ref "P2") (pin "RED4") (pinfunction "RED_RED4") (pintype "bidirectional"))
      (node (ref "P3") (pin "RED2") (pinfunction "RED_RED2") (pintype "bidirectional"))
      (node (ref "P3") (pin "RED4") (pinfunction "RED_RED4") (pintype "bidirectional"))
      (node (ref "P4") (pin "RED2") (pinfunction "RED_RED2") (pintype "bidirectional"))
      (node (ref "P4") (pin "RED4") (pinfunction "RED_RED4") (pintype "bidirectional"))
      (node (ref "P5") (pin "RED2") (pinfunction "RED_RED2") (pintype "bidirectional"))
      (node (ref "P5") (pin "RED4") (pinfunction "RED_RED4") (pintype "bidirectional"))
      (node (ref "ROW2") (pin "2") (pinfunction "2_2") (pintype "passive"))
    )
    (net (code "25") (name "/RED3") (class "Default")
      (node (ref "P10") (pin "RED1") (pinfunction "RED_RED1") (pintype "bidirectional"))
      (node (ref "P10") (pin "RED3") (pinfunction "RED_RED3") (pintype "bidirectional"))
      (node (ref "P6") (pin "RED1") (pinfunction "RED_RED1") (pintype "bidirectional"))
      (node (ref "P6") (pin "RED3") (pinfunction "RED_RED3") (pintype "bidirectional"))
      (node (ref "P7") (pin "RED1") (pinfunction "RED_RED1") (pintype "bidirectional"))
      (node (ref "P7") (pin "RED3") (pinfunction "RED_RED3") (pintype "bidirectional"))
      (node (ref "P8") (pin "RED1") (pinfunction "RED_RED1") (pintype "bidirectional"))
      (node (ref "P8") (pin "RED3") (pinfunction "RED_RED3") (pintype "bidirectional"))
      (node (ref "P9") (pin "RED1") (pinfunction "RED_RED1") (pintype "bidirectional"))
      (node (ref "P9") (pin "RED3") (pinfunction "RED_RED3") (pintype "bidirectional"))
      (node (ref "ROW3") (pin "2") (pinfunction "2_2") (pintype "passive"))
    )
    (net (code "26") (name "/RED4") (class "Default")
      (node (ref "P10") (pin "RED2") (pinfunction "RED_RED2") (pintype "bidirectional"))
      (node (ref "P10") (pin "RED4") (pinfunction "RED_RED4") (pintype "bidirectional"))
      (node (ref "P6") (pin "RED2") (pinfunction "RED_RED2") (pintype "bidirectional"))
      (node (ref "P6") (pin "RED4") (pinfunction "RED_RED4") (pintype "bidirectional"))
      (node (ref "P7") (pin "RED2") (pinfunction "RED_RED2") (pintype "bidirectional"))
      (node (ref "P7") (pin "RED4") (pinfunction "RED_RED4") (pintype "bidirectional"))
      (node (ref "P8") (pin "RED2") (pinfunction "RED_RED2") (pintype "bidirectional"))
      (node (ref "P8") (pin "RED4") (pinfunction "RED_RED4") (pintype "bidirectional"))
      (node (ref "P9") (pin "RED2") (pinfunction "RED_RED2") (pintype "bidirectional"))
      (node (ref "P9") (pin "RED4") (pinfunction "RED_RED4") (pintype "bidirectional"))
      (node (ref "ROW4") (pin "2") (pinfunction "2_2") (pintype "passive"))
    )
    (net (code "27") (name "/RED5") (class "Default")
      (node (ref "P11") (pin "RED1") (pinfunction "RED_RED1") (pintype "bidirectional"))
      (node (ref "P11") (pin "RED3") (pinfunction "RED_RED3") (pintype "bidirectional"))
      (node (ref "P12") (pin "RED1") (pinfunction "RED_RED1") (pintype "bidirectional"))
      (node (ref "P12") (pin "RED3") (pinfunction "RED_RED3") (pintype "bidirectional"))
      (node (ref "P13") (pin "RED1") (pinfunction "RED_RED1") (pintype "bidirectional"))
      (node (ref "P13") (pin "RED3") (pinfunction "RED_RED3") (pintype "bidirectional"))
      (node (ref "P14") (pin "RED1") (pinfunction "RED_RED1") (pintype "bidirectional"))
      (node (ref "P14") (pin "RED3") (pinfunction "RED_RED3") (pintype "bidirectional"))
      (node (ref "P15") (pin "RED1") (pinfunction "RED_RED1") (pintype "bidirectional"))
      (node (ref "P15") (pin "RED3") (pinfunction "RED_RED3") (pintype "bidirectional"))
      (node (ref "ROW5") (pin "2") (pinfunction "2_2") (pintype "passive"))
    )
    (net (code "28") (name "/RED6") (class "Default")
      (node (ref "P11") (pin "RED2") (pinfunction "RED_RED2") (pintype "bidirectional"))
      (node (ref "P11") (pin "RED4") (pinfunction "RED_RED4") (pintype "bidirectional"))
      (node (ref "P12") (pin "RED2") (pinfunction "RED_RED2") (pintype "bidirectional"))
      (node (ref "P12") (pin "RED4") (pinfunction "RED_RED4") (pintype "bidirectional"))
      (node (ref "P13") (pin "RED2") (pinfunction "RED_RED2") (pintype "bidirectional"))
      (node (ref "P13") (pin "RED4") (pinfunction "RED_RED4") (pintype "bidirectional"))
      (node (ref "P14") (pin "RED2") (pinfunction "RED_RED2") (pintype "bidirectional"))
      (node (ref "P14") (pin "RED4") (pinfunction "RED_RED4") (pintype "bidirectional"))
      (node (ref "P15") (pin "RED2") (pinfunction "RED_RED2") (pintype "bidirectional"))
      (node (ref "P15") (pin "RED4") (pinfunction "RED_RED4") (pintype "bidirectional"))
      (node (ref "ROW6") (pin "2") (pinfunction "2_2") (pintype "passive"))
    )
    (net (code "29") (name "/SWITCH1") (class "Default")
      (node (ref "P1") (pin "SIG1") (pinfunction "SIG1_SIG1") (pintype "bidirectional"))
      (node (ref "P1") (pin "SIG5") (pinfunction "SIG1_SIG5") (pintype "bidirectional"))
      (node (ref "P2") (pin "SIG1") (pinfunction "SIG1_SIG1") (pintype "bidirectional"))
      (node (ref "P2") (pin "SIG5") (pinfunction "SIG1_SIG5") (pintype "bidirectional"))
      (node (ref "P3") (pin "SIG1") (pinfunction "SIG1_SIG1") (pintype "bidirectional"))
      (node (ref "P3") (pin "SIG5") (pinfunction "SIG1_SIG5") (pintype "bidirectional"))
      (node (ref "P4") (pin "SIG1") (pinfunction "SIG1_SIG1") (pintype "bidirectional"))
      (node (ref "P4") (pin "SIG5") (pinfunction "SIG1_SIG5") (pintype "bidirectional"))
      (node (ref "P5") (pin "SIG1") (pinfunction "SIG1_SIG1") (pintype "bidirectional"))
      (node (ref "P5") (pin "SIG5") (pinfunction "SIG1_SIG5") (pintype "bidirectional"))
      (node (ref "ROW1") (pin "1") (pinfunction "1_1") (pintype "passive"))
    )
    (net (code "30") (name "/SWITCH2") (class "Default")
      (node (ref "P1") (pin "SIG3") (pinfunction "SIG1_SIG3") (pintype "bidirectional"))
      (node (ref "P1") (pin "SIG7") (pinfunction "SIG1_SIG7") (pintype "bidirectional"))
      (node (ref "P2") (pin "SIG3") (pinfunction "SIG1_SIG3") (pintype "bidirectional"))
      (node (ref "P2") (pin "SIG7") (pinfunction "SIG1_SIG7") (pintype "bidirectional"))
      (node (ref "P3") (pin "SIG3") (pinfunction "SIG1_SIG3") (pintype "bidirectional"))
      (node (ref "P3") (pin "SIG7") (pinfunction "SIG1_SIG7") (pintype "bidirectional"))
      (node (ref "P4") (pin "SIG3") (pinfunction "SIG1_SIG3") (pintype "bidirectional"))
      (node (ref "P4") (pin "SIG7") (pinfunction "SIG1_SIG7") (pintype "bidirectional"))
      (node (ref "P5") (pin "SIG3") (pinfunction "SIG1_SIG3") (pintype "bidirectional"))
      (node (ref "P5") (pin "SIG7") (pinfunction "SIG1_SIG7") (pintype "bidirectional"))
      (node (ref "ROW2") (pin "1") (pinfunction "1_1") (pintype "passive"))
    )
    (net (code "31") (name "/SWITCH3") (class "Default")
      (node (ref "P10") (pin "SIG1") (pinfunction "SIG1_SIG1") (pintype "bidirectional"))
      (node (ref "P10") (pin "SIG5") (pinfunction "SIG1_SIG5") (pintype "bidirectional"))
      (node (ref "P6") (pin "SIG1") (pinfunction "SIG1_SIG1") (pintype "bidirectional"))
      (node (ref "P6") (pin "SIG5") (pinfunction "SIG1_SIG5") (pintype "bidirectional"))
      (node (ref "P7") (pin "SIG1") (pinfunction "SIG1_SIG1") (pintype "bidirectional"))
      (node (ref "P7") (pin "SIG5") (pinfunction "SIG1_SIG5") (pintype "bidirectional"))
      (node (ref "P8") (pin "SIG1") (pinfunction "SIG1_SIG1") (pintype "bidirectional"))
      (node (ref "P8") (pin "SIG5") (pinfunction "SIG1_SIG5") (pintype "bidirectional"))
      (node (ref "P9") (pin "SIG1") (pinfunction "SIG1_SIG1") (pintype "bidirectional"))
      (node (ref "P9") (pin "SIG5") (pinfunction "SIG1_SIG5") (pintype "bidirectional"))
      (node (ref "ROW3") (pin "1") (pinfunction "1_1") (pintype "passive"))
    )
    (net (code "32") (name "/SWITCH4") (class "Default")
      (node (ref "P10") (pin "SIG3") (pinfunction "SIG1_SIG3") (pintype "bidirectional"))
      (node (ref "P10") (pin "SIG7") (pinfunction "SIG1_SIG7") (pintype "bidirectional"))
      (node (ref "P6") (pin "SIG3") (pinfunction "SIG1_SIG3") (pintype "bidirectional"))
      (node (ref "P6") (pin "SIG7") (pinfunction "SIG1_SIG7") (pintype "bidirectional"))
      (node (ref "P7") (pin "SIG3") (pinfunction "SIG1_SIG3") (pintype "bidirectional"))
      (node (ref "P7") (pin "SIG7") (pinfunction "SIG1_SIG7") (pintype "bidirectional"))
      (node (ref "P8") (pin "SIG3") (pinfunction "SIG1_SIG3") (pintype "bidirectional"))
      (node (ref "P8") (pin "SIG7") (pinfunction "SIG1_SIG7") (pintype "bidirectional"))
      (node (ref "P9") (pin "SIG3") (pinfunction "SIG1_SIG3") (pintype "bidirectional"))
      (node (ref "P9") (pin "SIG7") (pinfunction "SIG1_SIG7") (pintype "bidirectional"))
      (node (ref "ROW4") (pin "1") (pinfunction "1_1") (pintype "passive"))
    )
    (net (code "33") (name "/SWITCH5") (class "Default")
      (node (ref "P11") (pin "SIG1") (pinfunction "SIG1_SIG1") (pintype "bidirectional"))
      (node (ref "P11") (pin "SIG5") (pinfunction "SIG1_SIG5") (pintype "bidirectional"))
      (node (ref "P12") (pin "SIG1") (pinfunction "SIG1_SIG1") (pintype "bidirectional"))
      (node (ref "P12") (pin "SIG5") (pinfunction "SIG1_SIG5") (pintype "bidirectional"))
      (node (ref "P13") (pin "SIG1") (pinfunction "SIG1_SIG1") (pintype "bidirectional"))
      (node (ref "P13") (pin "SIG5") (pinfunction "SIG1_SIG5") (pintype "bidirectional"))
      (node (ref "P14") (pin "SIG1") (pinfunction "SIG1_SIG1") (pintype "bidirectional"))
      (node (ref "P14") (pin "SIG5") (pinfunction "SIG1_SIG5") (pintype "bidirectional"))
      (node (ref "P15") (pin "SIG1") (pinfunction "SIG1_SIG1") (pintype "bidirectional"))
      (node (ref "P15") (pin "SIG5") (pinfunction "SIG1_SIG5") (pintype "bidirectional"))
      (node (ref "ROW5") (pin "1") (pinfunction "1_1") (pintype "passive"))
    )
    (net (code "34") (name "/SWITCH6") (class "Default")
      (node (ref "P11") (pin "SIG3") (pinfunction "SIG1_SIG3") (pintype "bidirectional"))
      (node (ref "P11") (pin "SIG7") (pinfunction "SIG1_SIG7") (pintype "bidirectional"))
      (node (ref "P12") (pin "SIG3") (pinfunction "SIG1_SIG3") (pintype "bidirectional"))
      (node (ref "P12") (pin "SIG7") (pinfunction "SIG1_SIG7") (pintype "bidirectional"))
      (node (ref "P13") (pin "SIG3") (pinfunction "SIG1_SIG3") (pintype "bidirectional"))
      (node (ref "P13") (pin "SIG7") (pinfunction "SIG1_SIG7") (pintype "bidirectional"))
      (node (ref "P14") (pin "SIG3") (pinfunction "SIG1_SIG3") (pintype "bidirectional"))
      (node (ref "P14") (pin "SIG7") (pinfunction "SIG1_SIG7") (pintype "bidirectional"))
      (node (ref "P15") (pin "SIG3") (pinfunction "SIG1_SIG3") (pintype "bidirectional"))
      (node (ref "P15") (pin "SIG7") (pinfunction "SIG1_SIG7") (pintype "bidirectional"))
      (node (ref "ROW6") (pin "1") (pinfunction "1_1") (pintype "passive"))
    )
    (net (code "35") (name "/SWT-GND1") (class "Default")
      (node (ref "COL10") (pin "1") (pinfunction "1_1") (pintype "passive"))
      (node (ref "D1") (pin "P$1") (pinfunction "A_P$1") (pintype "passive"))
      (node (ref "D11") (pin "P$1") (pinfunction "A_P$1") (pintype "passive"))
      (node (ref "D21") (pin "P$1") (pinfunction "A_P$1") (pintype "passive"))
      (node (ref "D31") (pin "P$1") (pinfunction "A_P$1") (pintype "passive"))
      (node (ref "D41") (pin "P$1") (pinfunction "A_P$1") (pintype "passive"))
      (node (ref "D51") (pin "P$1") (pinfunction "A_P$1") (pintype "passive"))
    )
    (net (code "36") (name "/SWT-GND2") (class "Default")
      (node (ref "COL9") (pin "1") (pinfunction "1_1") (pintype "passive"))
      (node (ref "D12") (pin "P$1") (pinfunction "A_P$1") (pintype "passive"))
      (node (ref "D2") (pin "P$1") (pinfunction "A_P$1") (pintype "passive"))
      (node (ref "D22") (pin "P$1") (pinfunction "A_P$1") (pintype "passive"))
      (node (ref "D32") (pin "P$1") (pinfunction "A_P$1") (pintype "passive"))
      (node (ref "D42") (pin "P$1") (pinfunction "A_P$1") (pintype "passive"))
      (node (ref "D52") (pin "P$1") (pinfunction "A_P$1") (pintype "passive"))
    )
    (net (code "37") (name "/SWT-GND3") (class "Default")
      (node (ref "COL8") (pin "1") (pinfunction "1_1") (pintype "passive"))
      (node (ref "D13") (pin "P$1") (pinfunction "A_P$1") (pintype "passive"))
      (node (ref "D23") (pin "P$1") (pinfunction "A_P$1") (pintype "passive"))
      (node (ref "D3") (pin "P$1") (pinfunction "A_P$1") (pintype "passive"))
      (node (ref "D33") (pin "P$1") (pinfunction "A_P$1") (pintype "passive"))
      (node (ref "D43") (pin "P$1") (pinfunction "A_P$1") (pintype "passive"))
      (node (ref "D53") (pin "P$1") (pinfunction "A_P$1") (pintype "passive"))
    )
    (net (code "38") (name "/SWT-GND4") (class "Default")
      (node (ref "COL7") (pin "1") (pinfunction "1_1") (pintype "passive"))
      (node (ref "D14") (pin "P$1") (pinfunction "A_P$1") (pintype "passive"))
      (node (ref "D24") (pin "P$1") (pinfunction "A_P$1") (pintype "passive"))
      (node (ref "D34") (pin "P$1") (pinfunction "A_P$1") (pintype "passive"))
      (node (ref "D4") (pin "P$1") (pinfunction "A_P$1") (pintype "passive"))
      (node (ref "D44") (pin "P$1") (pinfunction "A_P$1") (pintype "passive"))
      (node (ref "D54") (pin "P$1") (pinfunction "A_P$1") (pintype "passive"))
    )
    (net (code "39") (name "/SWT-GND5") (class "Default")
      (node (ref "COL6") (pin "1") (pinfunction "1_1") (pintype "passive"))
      (node (ref "D15") (pin "P$1") (pinfunction "A_P$1") (pintype "passive"))
      (node (ref "D25") (pin "P$1") (pinfunction "A_P$1") (pintype "passive"))
      (node (ref "D35") (pin "P$1") (pinfunction "A_P$1") (pintype "passive"))
      (node (ref "D45") (pin "P$1") (pinfunction "A_P$1") (pintype "passive"))
      (node (ref "D5") (pin "P$1") (pinfunction "A_P$1") (pintype "passive"))
      (node (ref "D55") (pin "P$1") (pinfunction "A_P$1") (pintype "passive"))
    )
    (net (code "40") (name "/SWT-GND6") (class "Default")
      (node (ref "COL5") (pin "1") (pinfunction "1_1") (pintype "passive"))
      (node (ref "D16") (pin "P$1") (pinfunction "A_P$1") (pintype "passive"))
      (node (ref "D26") (pin "P$1") (pinfunction "A_P$1") (pintype "passive"))
      (node (ref "D36") (pin "P$1") (pinfunction "A_P$1") (pintype "passive"))
      (node (ref "D46") (pin "P$1") (pinfunction "A_P$1") (pintype "passive"))
      (node (ref "D56") (pin "P$1") (pinfunction "A_P$1") (pintype "passive"))
      (node (ref "D6") (pin "P$1") (pinfunction "A_P$1") (pintype "passive"))
    )
    (net (code "41") (name "/SWT-GND7") (class "Default")
      (node (ref "COL4") (pin "1") (pinfunction "1_1") (pintype "passive"))
      (node (ref "D17") (pin "P$1") (pinfunction "A_P$1") (pintype "passive"))
      (node (ref "D27") (pin "P$1") (pinfunction "A_P$1") (pintype "passive"))
      (node (ref "D37") (pin "P$1") (pinfunction "A_P$1") (pintype "passive"))
      (node (ref "D47") (pin "P$1") (pinfunction "A_P$1") (pintype "passive"))
      (node (ref "D57") (pin "P$1") (pinfunction "A_P$1") (pintype "passive"))
      (node (ref "D7") (pin "P$1") (pinfunction "A_P$1") (pintype "passive"))
    )
    (net (code "42") (name "/SWT-GND8") (class "Default")
      (node (ref "COL3") (pin "1") (pinfunction "1_1") (pintype "passive"))
      (node (ref "D18") (pin "P$1") (pinfunction "A_P$1") (pintype "passive"))
      (node (ref "D28") (pin "P$1") (pinfunction "A_P$1") (pintype "passive"))
      (node (ref "D38") (pin "P$1") (pinfunction "A_P$1") (pintype "passive"))
      (node (ref "D48") (pin "P$1") (pinfunction "A_P$1") (pintype "passive"))
      (node (ref "D58") (pin "P$1") (pinfunction "A_P$1") (pintype "passive"))
      (node (ref "D8") (pin "P$1") (pinfunction "A_P$1") (pintype "passive"))
    )
    (net (code "43") (name "/SWT-GND9") (class "Default")
      (node (ref "COL2") (pin "1") (pinfunction "1_1") (pintype "passive"))
      (node (ref "D19") (pin "P$1") (pinfunction "A_P$1") (pintype "passive"))
      (node (ref "D29") (pin "P$1") (pinfunction "A_P$1") (pintype "passive"))
      (node (ref "D39") (pin "P$1") (pinfunction "A_P$1") (pintype "passive"))
      (node (ref "D49") (pin "P$1") (pinfunction "A_P$1") (pintype "passive"))
      (node (ref "D59") (pin "P$1") (pinfunction "A_P$1") (pintype "passive"))
      (node (ref "D9") (pin "P$1") (pinfunction "A_P$1") (pintype "passive"))
    )
    (net (code "44") (name "/SWT-GND10") (class "Default")
      (node (ref "COL1") (pin "1") (pinfunction "1_1") (pintype "passive"))
      (node (ref "D10") (pin "P$1") (pinfunction "A_P$1") (pintype "passive"))
      (node (ref "D20") (pin "P$1") (pinfunction "A_P$1") (pintype "passive"))
      (node (ref "D30") (pin "P$1") (pinfunction "A_P$1") (pintype "passive"))
      (node (ref "D40") (pin "P$1") (pinfunction "A_P$1") (pintype "passive"))
      (node (ref "D50") (pin "P$1") (pinfunction "A_P$1") (pintype "passive"))
      (node (ref "D60") (pin "P$1") (pinfunction "A_P$1") (pintype "passive"))
    )
    (net (code "46") (name "Net-(D1-C)") (class "Default")
      (node (ref "D1") (pin "P$2") (pinfunction "C_P$2") (pintype "passive"))
      (node (ref "P1") (pin "SIG6") (pinfunction "SIG2_SIG6") (pintype "bidirectional"))
    )
    (net (code "47") (name "Net-(D2-C)") (class "Default")
      (node (ref "D2") (pin "P$2") (pinfunction "C_P$2") (pintype "passive"))
      (node (ref "P1") (pin "SIG2") (pinfunction "SIG2_SIG2") (pintype "bidirectional"))
    )
    (net (code "48") (name "Net-(D3-C)") (class "Default")
      (node (ref "D3") (pin "P$2") (pinfunction "C_P$2") (pintype "passive"))
      (node (ref "P2") (pin "SIG6") (pinfunction "SIG2_SIG6") (pintype "bidirectional"))
    )
    (net (code "49") (name "Net-(D4-C)") (class "Default")
      (node (ref "D4") (pin "P$2") (pinfunction "C_P$2") (pintype "passive"))
      (node (ref "P2") (pin "SIG2") (pinfunction "SIG2_SIG2") (pintype "bidirectional"))
    )
    (net (code "50") (name "Net-(D5-C)") (class "Default")
      (node (ref "D5") (pin "P$2") (pinfunction "C_P$2") (pintype "passive"))
      (node (ref "P3") (pin "SIG6") (pinfunction "SIG2_SIG6") (pintype "bidirectional"))
    )
    (net (code "51") (name "Net-(D6-C)") (class "Default")
      (node (ref "D6") (pin "P$2") (pinfunction "C_P$2") (pintype "passive"))
      (node (ref "P3") (pin "SIG2") (pinfunction "SIG2_SIG2") (pintype "bidirectional"))
    )
    (net (code "52") (name "Net-(D7-C)") (class "Default")
      (node (ref "D7") (pin "P$2") (pinfunction "C_P$2") (pintype "passive"))
      (node (ref "P4") (pin "SIG6") (pinfunction "SIG2_SIG6") (pintype "bidirectional"))
    )
    (net (code "53") (name "Net-(D8-C)") (class "Default")
      (node (ref "D8") (pin "P$2") (pinfunction "C_P$2") (pintype "passive"))
      (node (ref "P4") (pin "SIG2") (pinfunction "SIG2_SIG2") (pintype "bidirectional"))
    )
    (net (code "54") (name "Net-(D9-C)") (class "Default")
      (node (ref "D9") (pin "P$2") (pinfunction "C_P$2") (pintype "passive"))
      (node (ref "P5") (pin "SIG6") (pinfunction "SIG2_SIG6") (pintype "bidirectional"))
    )
    (net (code "55") (name "Net-(D10-C)") (class "Default")
      (node (ref "D10") (pin "P$2") (pinfunction "C_P$2") (pintype "passive"))
      (node (ref "P5") (pin "SIG2") (pinfunction "SIG2_SIG2") (pintype "bidirectional"))
    )
    (net (code "56") (name "Net-(D11-C)") (class "Default")
      (node (ref "D11") (pin "P$2") (pinfunction "C_P$2") (pintype "passive"))
      (node (ref "P1") (pin "SIG8") (pinfunction "SIG2_SIG8") (pintype "bidirectional"))
    )
    (net (code "57") (name "Net-(D12-C)") (class "Default")
      (node (ref "D12") (pin "P$2") (pinfunction "C_P$2") (pintype "passive"))
      (node (ref "P1") (pin "SIG4") (pinfunction "SIG2_SIG4") (pintype "bidirectional"))
    )
    (net (code "58") (name "Net-(D13-C)") (class "Default")
      (node (ref "D13") (pin "P$2") (pinfunction "C_P$2") (pintype "passive"))
      (node (ref "P2") (pin "SIG8") (pinfunction "SIG2_SIG8") (pintype "bidirectional"))
    )
    (net (code "59") (name "Net-(D14-C)") (class "Default")
      (node (ref "D14") (pin "P$2") (pinfunction "C_P$2") (pintype "passive"))
      (node (ref "P2") (pin "SIG4") (pinfunction "SIG2_SIG4") (pintype "bidirectional"))
    )
    (net (code "60") (name "Net-(D15-C)") (class "Default")
      (node (ref "D15") (pin "P$2") (pinfunction "C_P$2") (pintype "passive"))
      (node (ref "P3") (pin "SIG8") (pinfunction "SIG2_SIG8") (pintype "bidirectional"))
    )
    (net (code "61") (name "Net-(D16-C)") (class "Default")
      (node (ref "D16") (pin "P$2") (pinfunction "C_P$2") (pintype "passive"))
      (node (ref "P3") (pin "SIG4") (pinfunction "SIG2_SIG4") (pintype "bidirectional"))
    )
    (net (code "62") (name "Net-(D17-C)") (class "Default")
      (node (ref "D17") (pin "P$2") (pinfunction "C_P$2") (pintype "passive"))
      (node (ref "P4") (pin "SIG8") (pinfunction "SIG2_SIG8") (pintype "bidirectional"))
    )
    (net (code "63") (name "Net-(D18-C)") (class "Default")
      (node (ref "D18") (pin "P$2") (pinfunction "C_P$2") (pintype "passive"))
      (node (ref "P4") (pin "SIG4") (pinfunction "SIG2_SIG4") (pintype "bidirectional"))
    )
    (net (code "64") (name "Net-(D19-C)") (class "Default")
      (node (ref "D19") (pin "P$2") (pinfunction "C_P$2") (pintype "passive"))
      (node (ref "P5") (pin "SIG8") (pinfunction "SIG2_SIG8") (pintype "bidirectional"))
    )
    (net (code "65") (name "Net-(D20-C)") (class "Default")
      (node (ref "D20") (pin "P$2") (pinfunction "C_P$2") (pintype "passive"))
      (node (ref "P5") (pin "SIG4") (pinfunction "SIG2_SIG4") (pintype "bidirectional"))
    )
    (net (code "66") (name "Net-(D21-C)") (class "Default")
      (node (ref "D21") (pin "P$2") (pinfunction "C_P$2") (pintype "passive"))
      (node (ref "P6") (pin "SIG6") (pinfunction "SIG2_SIG6") (pintype "bidirectional"))
    )
    (net (code "67") (name "Net-(D22-C)") (class "Default")
      (node (ref "D22") (pin "P$2") (pinfunction "C_P$2") (pintype "passive"))
      (node (ref "P6") (pin "SIG2") (pinfunction "SIG2_SIG2") (pintype "bidirectional"))
    )
    (net (code "68") (name "Net-(D23-C)") (class "Default")
      (node (ref "D23") (pin "P$2") (pinfunction "C_P$2") (pintype "passive"))
      (node (ref "P7") (pin "SIG6") (pinfunction "SIG2_SIG6") (pintype "bidirectional"))
    )
    (net (code "69") (name "Net-(D24-C)") (class "Default")
      (node (ref "D24") (pin "P$2") (pinfunction "C_P$2") (pintype "passive"))
      (node (ref "P7") (pin "SIG2") (pinfunction "SIG2_SIG2") (pintype "bidirectional"))
    )
    (net (code "70") (name "Net-(D25-C)") (class "Default")
      (node (ref "D25") (pin "P$2") (pinfunction "C_P$2") (pintype "passive"))
      (node (ref "P8") (pin "SIG6") (pinfunction "SIG2_SIG6") (pintype "bidirectional"))
    )
    (net (code "71") (name "Net-(D26-C)") (class "Default")
      (node (ref "D26") (pin "P$2") (pinfunction "C_P$2") (pintype "passive"))
      (node (ref "P8") (pin "SIG2") (pinfunction "SIG2_SIG2") (pintype "bidirectional"))
    )
    (net (code "72") (name "Net-(D27-C)") (class "Default")
      (node (ref "D27") (pin "P$2") (pinfunction "C_P$2") (pintype "passive"))
      (node (ref "P9") (pin "SIG6") (pinfunction "SIG2_SIG6") (pintype "bidirectional"))
    )
    (net (code "73") (name "Net-(D28-C)") (class "Default")
      (node (ref "D28") (pin "P$2") (pinfunction "C_P$2") (pintype "passive"))
      (node (ref "P9") (pin "SIG2") (pinfunction "SIG2_SIG2") (pintype "bidirectional"))
    )
    (net (code "74") (name "Net-(D29-C)") (class "Default")
      (node (ref "D29") (pin "P$2") (pinfunction "C_P$2") (pintype "passive"))
      (node (ref "P10") (pin "SIG6") (pinfunction "SIG2_SIG6") (pintype "bidirectional"))
    )
    (net (code "75") (name "Net-(D30-C)") (class "Default")
      (node (ref "D30") (pin "P$2") (pinfunction "C_P$2") (pintype "passive"))
      (node (ref "P10") (pin "SIG2") (pinfunction "SIG2_SIG2") (pintype "bidirectional"))
    )
    (net (code "76") (name "Net-(D31-C)") (class "Default")
      (node (ref "D31") (pin "P$2") (pinfunction "C_P$2") (pintype "passive"))
      (node (ref "P6") (pin "SIG8") (pinfunction "SIG2_SIG8") (pintype "bidirectional"))
    )
    (net (code "77") (name "Net-(D32-C)") (class "Default")
      (node (ref "D32") (pin "P$2") (pinfunction "C_P$2") (pintype "passive"))
      (node (ref "P6") (pin "SIG4") (pinfunction "SIG2_SIG4") (pintype "bidirectional"))
    )
    (net (code "78") (name "Net-(D33-C)") (class "Default")
      (node (ref "D33") (pin "P$2") (pinfunction "C_P$2") (pintype "passive"))
      (node (ref "P7") (pin "SIG8") (pinfunction "SIG2_SIG8") (pintype "bidirectional"))
    )
    (net (code "79") (name "Net-(D34-C)") (class "Default")
      (node (ref "D34") (pin "P$2") (pinfunction "C_P$2") (pintype "passive"))
      (node (ref "P7") (pin "SIG4") (pinfunction "SIG2_SIG4") (pintype "bidirectional"))
    )
    (net (code "80") (name "Net-(D35-C)") (class "Default")
      (node (ref "D35") (pin "P$2") (pinfunction "C_P$2") (pintype "passive"))
      (node (ref "P8") (pin "SIG8") (pinfunction "SIG2_SIG8") (pintype "bidirectional"))
    )
    (net (code "81") (name "Net-(D36-C)") (class "Default")
      (node (ref "D36") (pin "P$2") (pinfunction "C_P$2") (pintype "passive"))
      (node (ref "P8") (pin "SIG4") (pinfunction "SIG2_SIG4") (pintype "bidirectional"))
    )
    (net (code "82") (name "Net-(D37-C)") (class "Default")
      (node (ref "D37") (pin "P$2") (pinfunction "C_P$2") (pintype "passive"))
      (node (ref "P9") (pin "SIG8") (pinfunction "SIG2_SIG8") (pintype "bidirectional"))
    )
    (net (code "83") (name "Net-(D38-C)") (class "Default")
      (node (ref "D38") (pin "P$2") (pinfunction "C_P$2") (pintype "passive"))
      (node (ref "P9") (pin "SIG4") (pinfunction "SIG2_SIG4") (pintype "bidirectional"))
    )
    (net (code "84") (name "Net-(D39-C)") (class "Default")
      (node (ref "D39") (pin "P$2") (pinfunction "C_P$2") (pintype "passive"))
      (node (ref "P10") (pin "SIG8") (pinfunction "SIG2_SIG8") (pintype "bidirectional"))
    )
    (net (code "85") (name "Net-(D40-C)") (class "Default")
      (node (ref "D40") (pin "P$2") (pinfunction "C_P$2") (pintype "passive"))
      (node (ref "P10") (pin "SIG4") (pinfunction "SIG2_SIG4") (pintype "bidirectional"))
    )
    (net (code "86") (name "Net-(D41-C)") (class "Default")
      (node (ref "D41") (pin "P$2") (pinfunction "C_P$2") (pintype "passive"))
      (node (ref "P11") (pin "SIG6") (pinfunction "SIG2_SIG6") (pintype "bidirectional"))
    )
    (net (code "87") (name "Net-(D42-C)") (class "Default")
      (node (ref "D42") (pin "P$2") (pinfunction "C_P$2") (pintype "passive"))
      (node (ref "P11") (pin "SIG2") (pinfunction "SIG2_SIG2") (pintype "bidirectional"))
    )
    (net (code "88") (name "Net-(D43-C)") (class "Default")
      (node (ref "D43") (pin "P$2") (pinfunction "C_P$2") (pintype "passive"))
      (node (ref "P12") (pin "SIG6") (pinfunction "SIG2_SIG6") (pintype "bidirectional"))
    )
    (net (code "89") (name "Net-(D44-C)") (class "Default")
      (node (ref "D44") (pin "P$2") (pinfunction "C_P$2") (pintype "passive"))
      (node (ref "P12") (pin "SIG2") (pinfunction "SIG2_SIG2") (pintype "bidirectional"))
    )
    (net (code "90") (name "Net-(D45-C)") (class "Default")
      (node (ref "D45") (pin "P$2") (pinfunction "C_P$2") (pintype "passive"))
      (node (ref "P13") (pin "SIG6") (pinfunction "SIG2_SIG6") (pintype "bidirectional"))
    )
    (net (code "91") (name "Net-(D46-C)") (class "Default")
      (node (ref "D46") (pin "P$2") (pinfunction "C_P$2") (pintype "passive"))
      (node (ref "P13") (pin "SIG2") (pinfunction "SIG2_SIG2") (pintype "bidirectional"))
    )
    (net (code "92") (name "Net-(D47-C)") (class "Default")
      (node (ref "D47") (pin "P$2") (pinfunction "C_P$2") (pintype "passive"))
      (node (ref "P14") (pin "SIG6") (pinfunction "SIG2_SIG6") (pintype "bidirectional"))
    )
    (net (code "93") (name "Net-(D48-C)") (class "Default")
      (node (ref "D48") (pin "P$2") (pinfunction "C_P$2") (pintype "passive"))
      (node (ref "P14") (pin "SIG2") (pinfunction "SIG2_SIG2") (pintype "bidirectional"))
    )
    (net (code "94") (name "Net-(D49-C)") (class "Default")
      (node (ref "D49") (pin "P$2") (pinfunction "C_P$2") (pintype "passive"))
      (node (ref "P15") (pin "SIG6") (pinfunction "SIG2_SIG6") (pintype "bidirectional"))
    )
    (net (code "95") (name "Net-(D50-C)") (class "Default")
      (node (ref "D50") (pin "P$2") (pinfunction "C_P$2") (pintype "passive"))
      (node (ref "P15") (pin "SIG2") (pinfunction "SIG2_SIG2") (pintype "bidirectional"))
    )
    (net (code "96") (name "Net-(D51-C)") (class "Default")
      (node (ref "D51") (pin "P$2") (pinfunction "C_P$2") (pintype "passive"))
      (node (ref "P11") (pin "SIG8") (pinfunction "SIG2_SIG8") (pintype "bidirectional"))
    )
    (net (code "97") (name "Net-(D52-C)") (class "Default")
      (node (ref "D52") (pin "P$2") (pinfunction "C_P$2") (pintype "passive"))
      (node (ref "P11") (pin "SIG4") (pinfunction "SIG2_SIG4") (pintype "bidirectional"))
    )
    (net (code "98") (name "Net-(D53-C)") (class "Default")
      (node (ref "D53") (pin "P$2") (pinfunction "C_P$2") (pintype "passive"))
      (node (ref "P12") (pin "SIG8") (pinfunction "SIG2_SIG8") (pintype "bidirectional"))
    )
    (net (code "99") (name "Net-(D54-C)") (class "Default")
      (node (ref "D54") (pin "P$2") (pinfunction "C_P$2") (pintype "passive"))
      (node (ref "P12") (pin "SIG4") (pinfunction "SIG2_SIG4") (pintype "bidirectional"))
    )
    (net (code "100") (name "Net-(D55-C)") (class "Default")
      (node (ref "D55") (pin "P$2") (pinfunction "C_P$2") (pintype "passive"))
      (node (ref "P13") (pin "SIG8") (pinfunction "SIG2_SIG8") (pintype "bidirectional"))
    )
    (net (code "101") (name "Net-(D56-C)") (class "Default")
      (node (ref "D56") (pin "P$2") (pinfunction "C_P$2") (pintype "passive"))
      (node (ref "P13") (pin "SIG4") (pinfunction "SIG2_SIG4") (pintype "bidirectional"))
    )
    (net (code "102") (name "Net-(D57-C)") (class "Default")
      (node (ref "D57") (pin "P$2") (pinfunction "C_P$2") (pintype "passive"))
      (node (ref "P14") (pin "SIG8") (pinfunction "SIG2_SIG8") (pintype "bidirectional"))
    )
    (net (code "103") (name "Net-(D58-C)") (class "Default")
      (node (ref "D58") (pin "P$2") (pinfunction "C_P$2") (pintype "passive"))
      (node (ref "P14") (pin "SIG4") (pinfunction "SIG2_SIG4") (pintype "bidirectional"))
    )
    (net (code "104") (name "Net-(D59-C)") (class "Default")
      (node (ref "D59") (pin "P$2") (pinfunction "C_P$2") (pintype "passive"))
      (node (ref "P15") (pin "SIG8") (pinfunction "SIG2_SIG8") (pintype "bidirectional"))
    )
    (net (code "105") (name "Net-(D60-C)") (class "Default")
      (node (ref "D60") (pin "P$2") (pinfunction "C_P$2") (pintype "passive"))
      (node (ref "P15") (pin "SIG4") (pinfunction "SIG2_SIG4") (pintype "bidirectional"))
    )
  )
)
